# mbed-WiFi-BLE-Cloud-v1_1_0.net
KiCad netlist of a schematic drawn in EAGLE
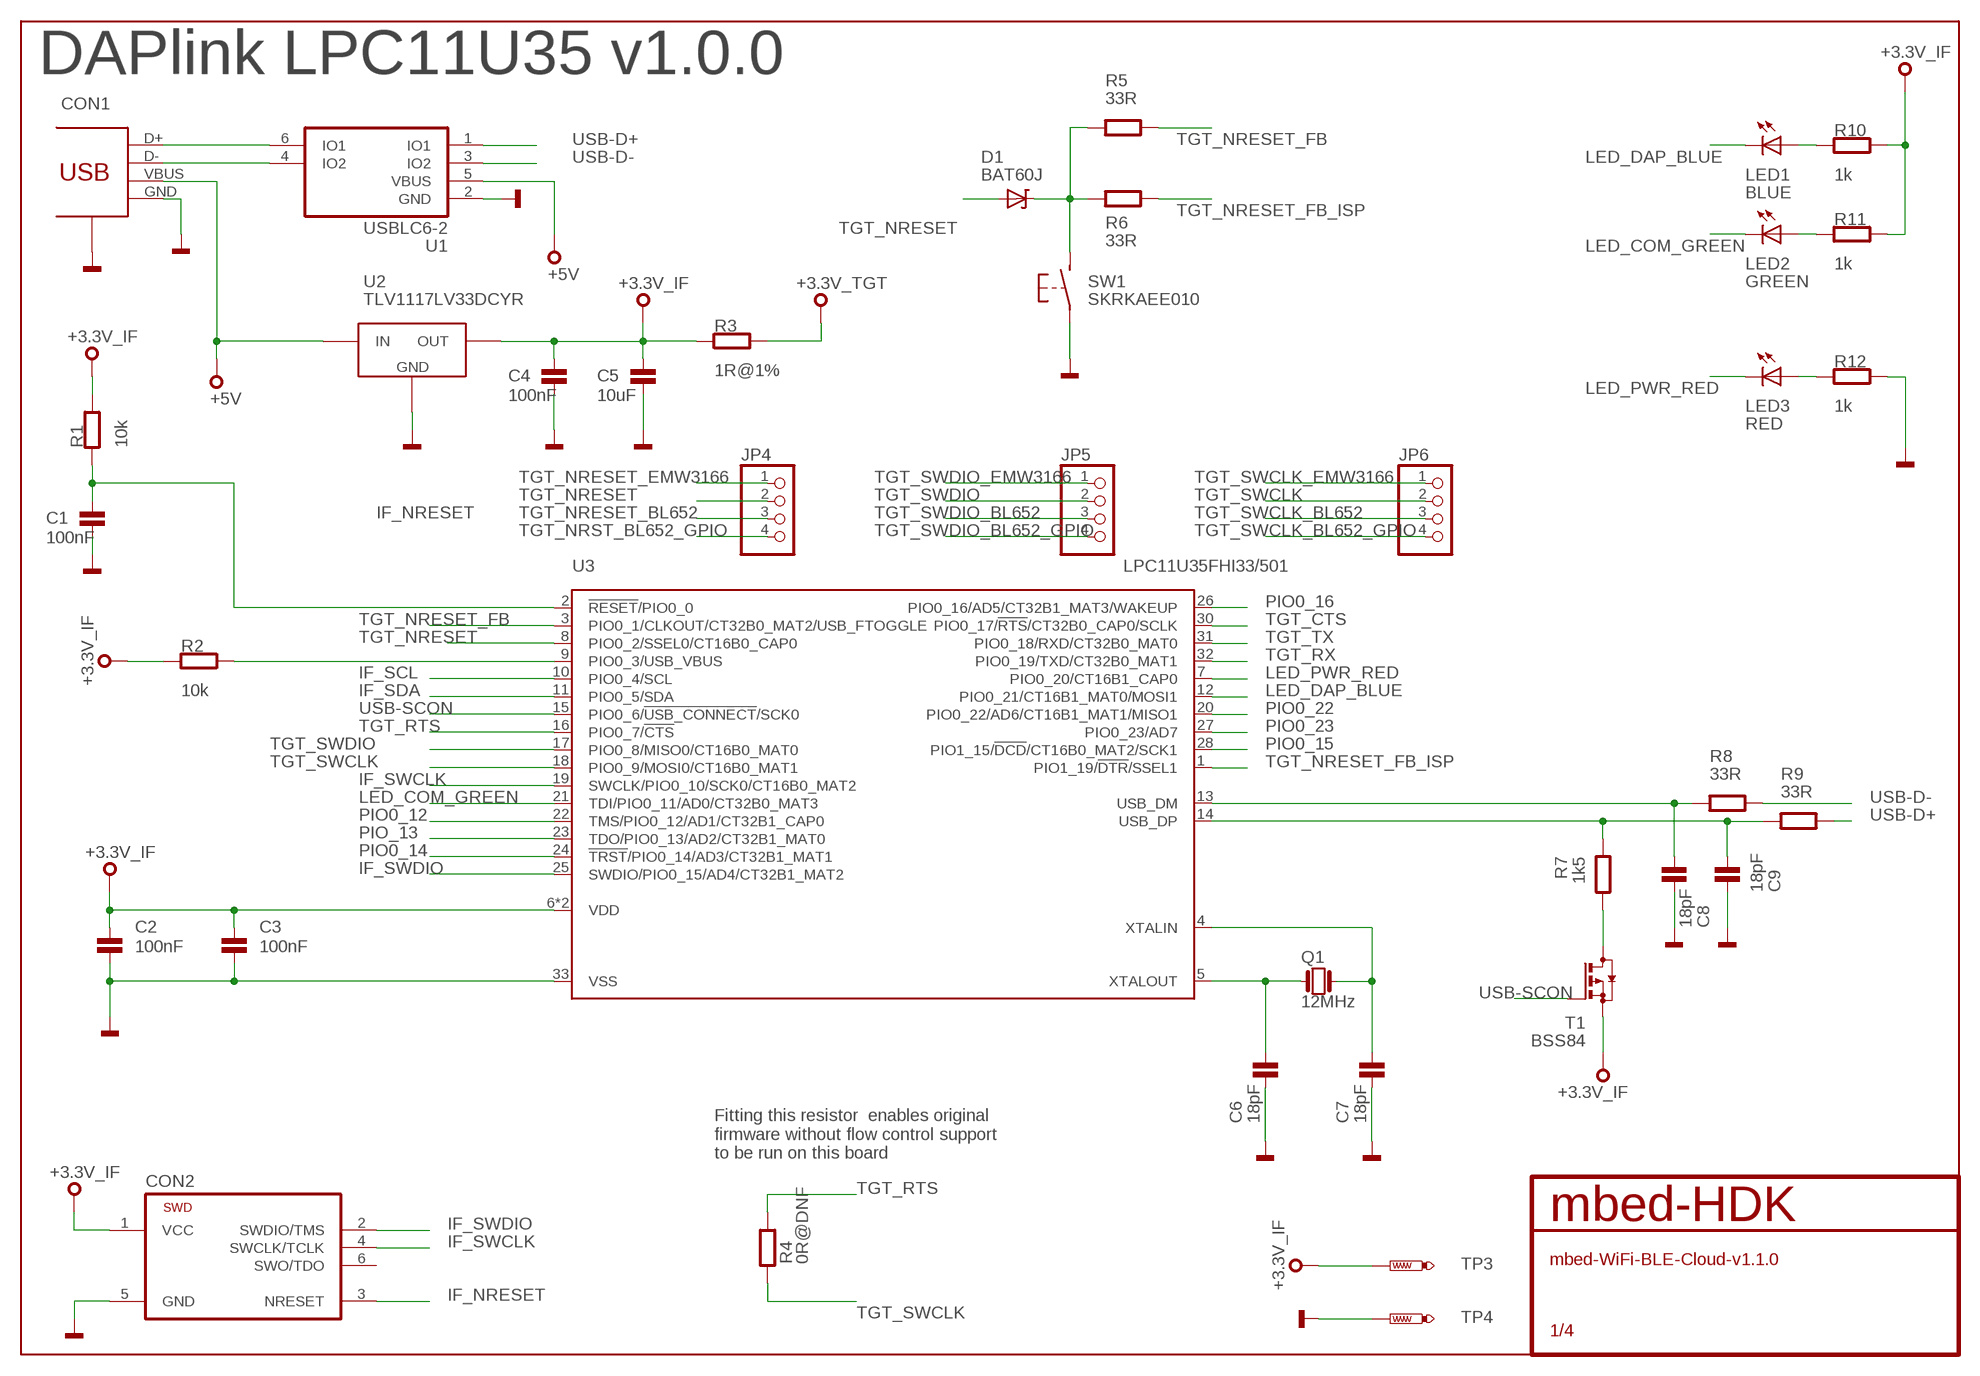
[diagram p0: schematic, sheet 1]
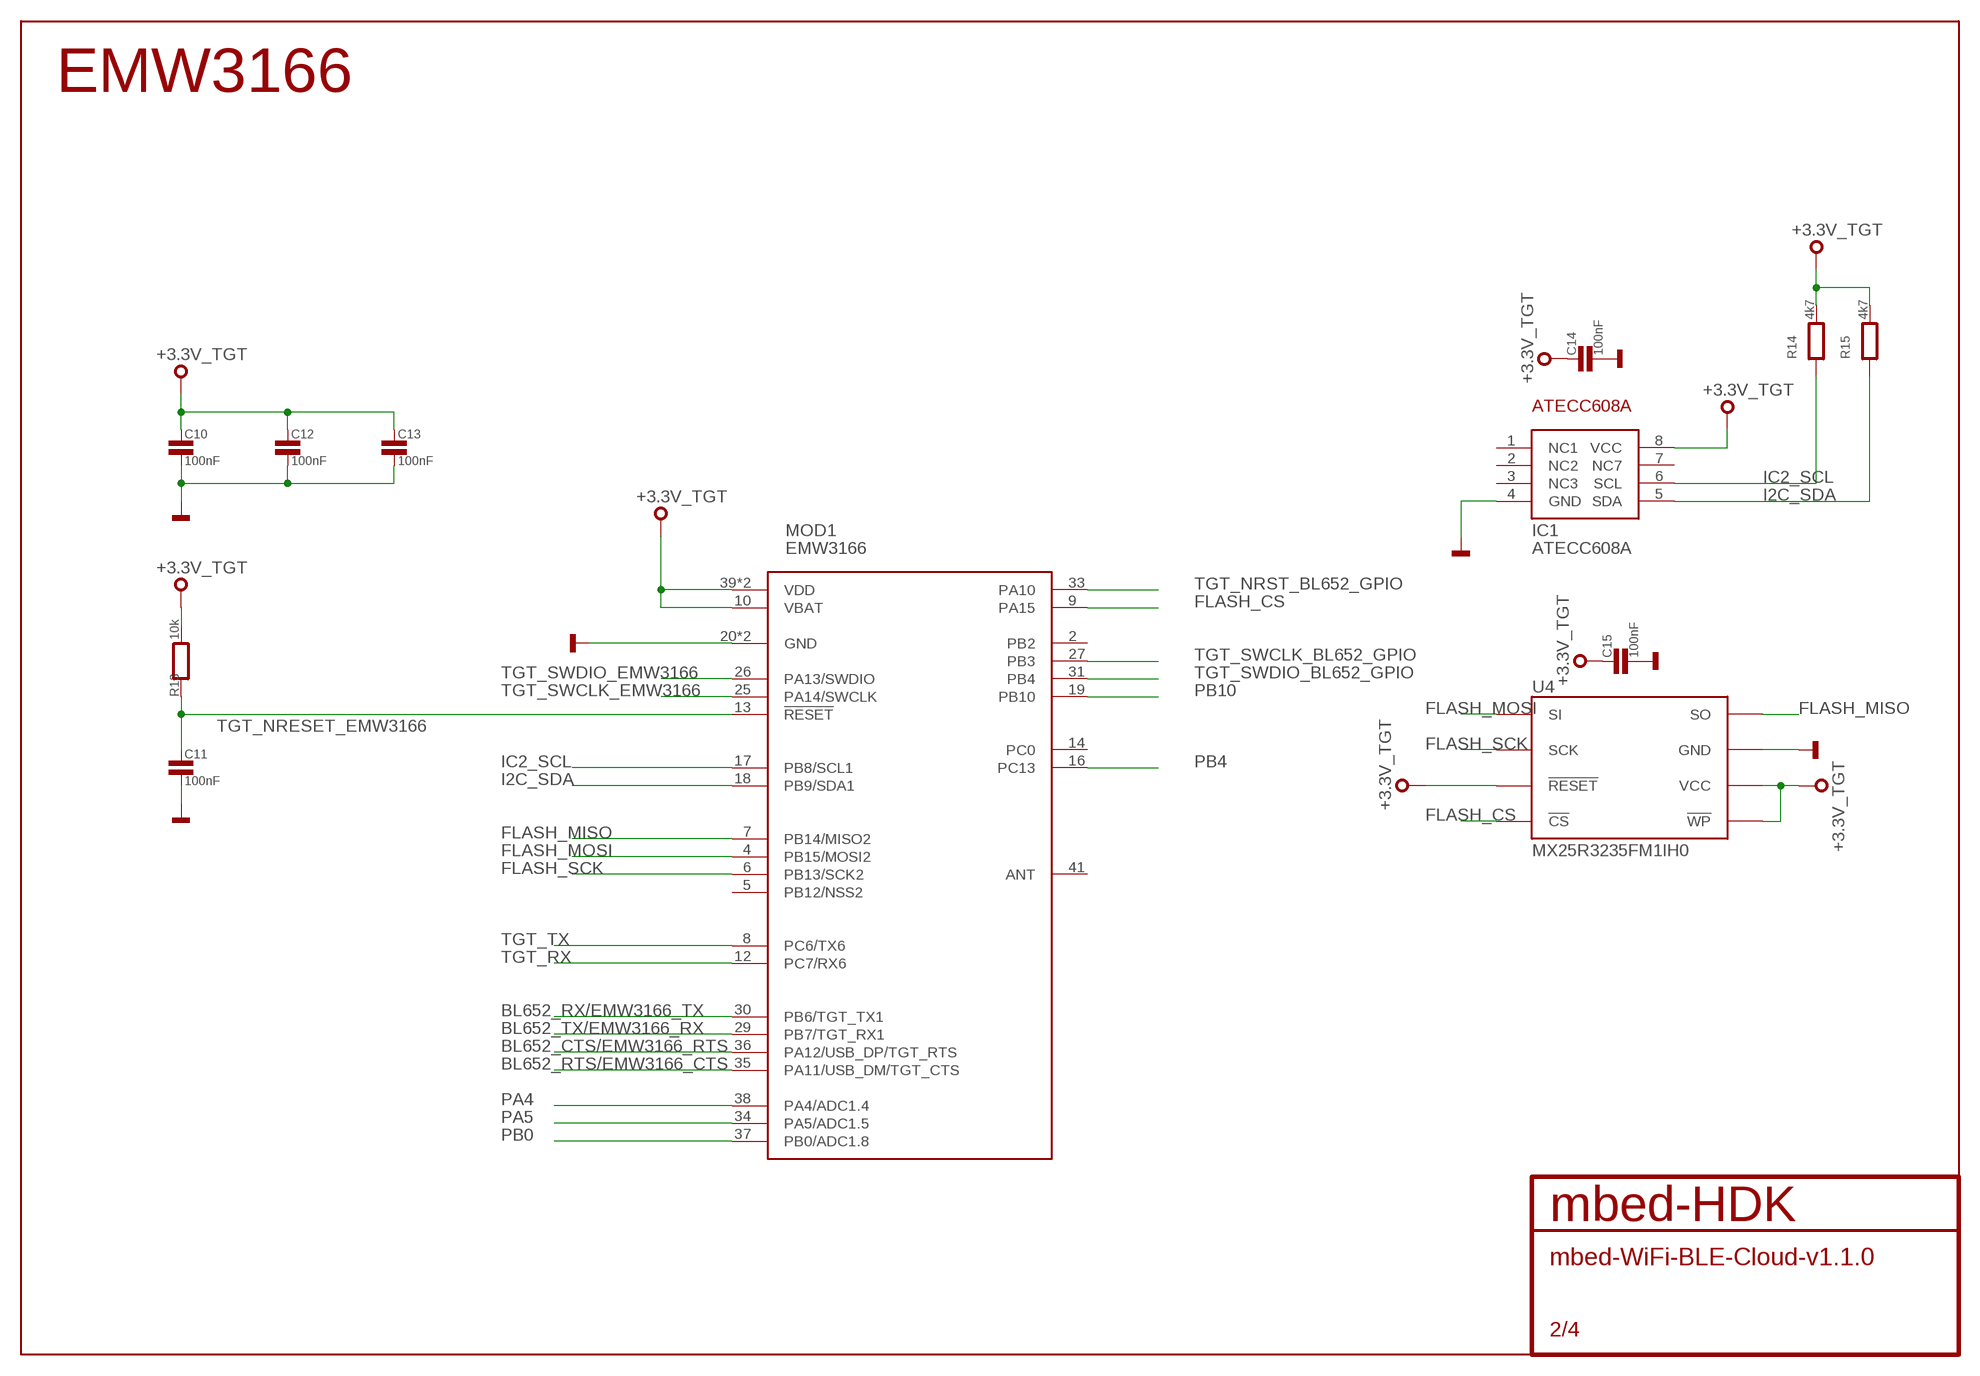
[diagram p1: schematic, sheet 2]
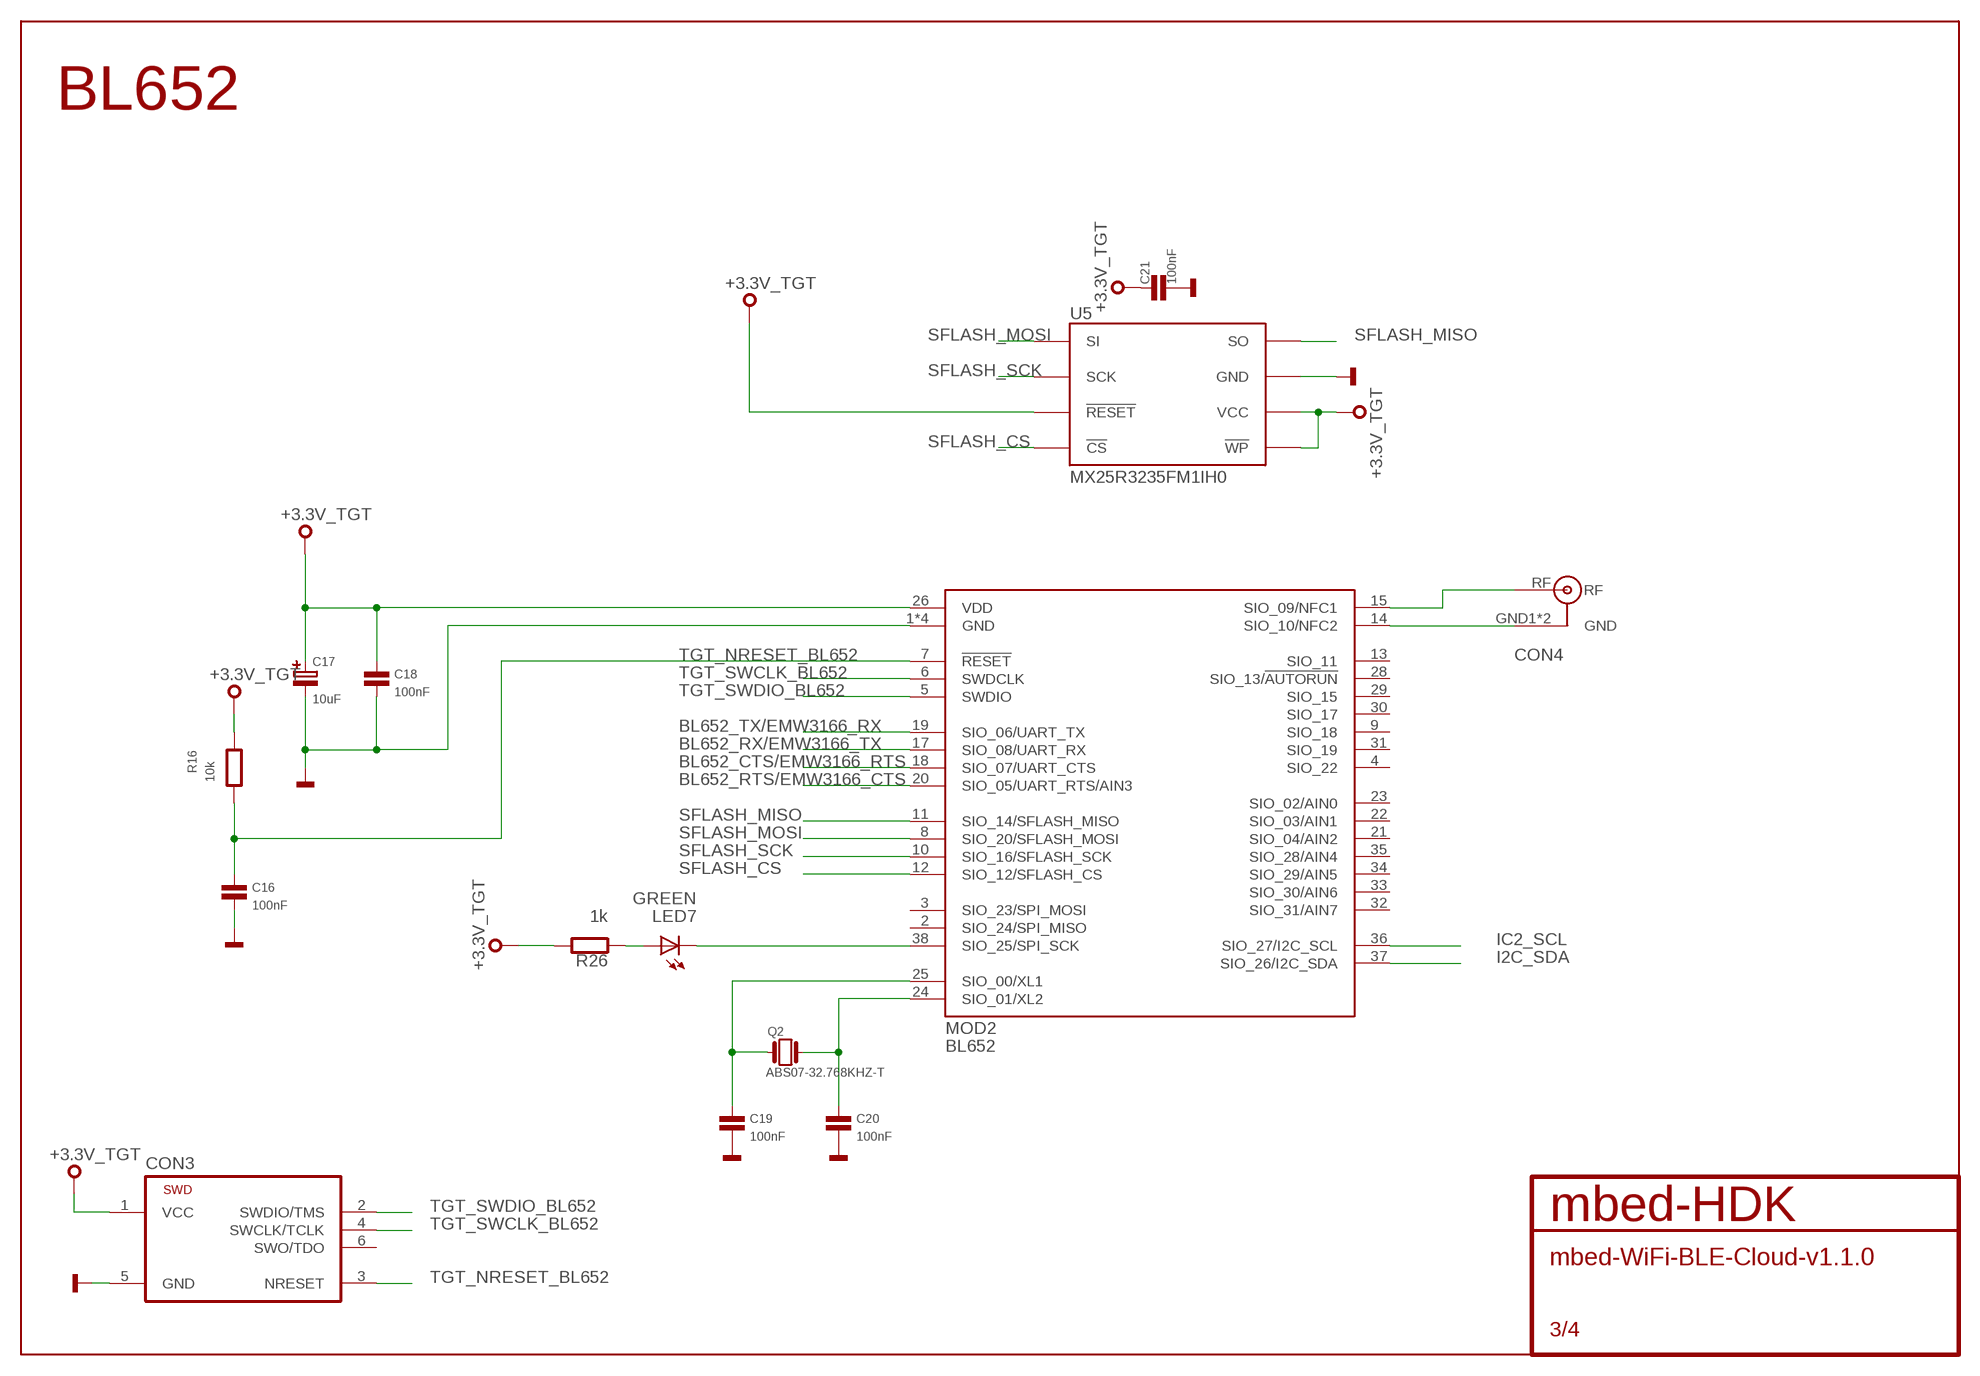
[diagram p2: schematic, sheet 3]
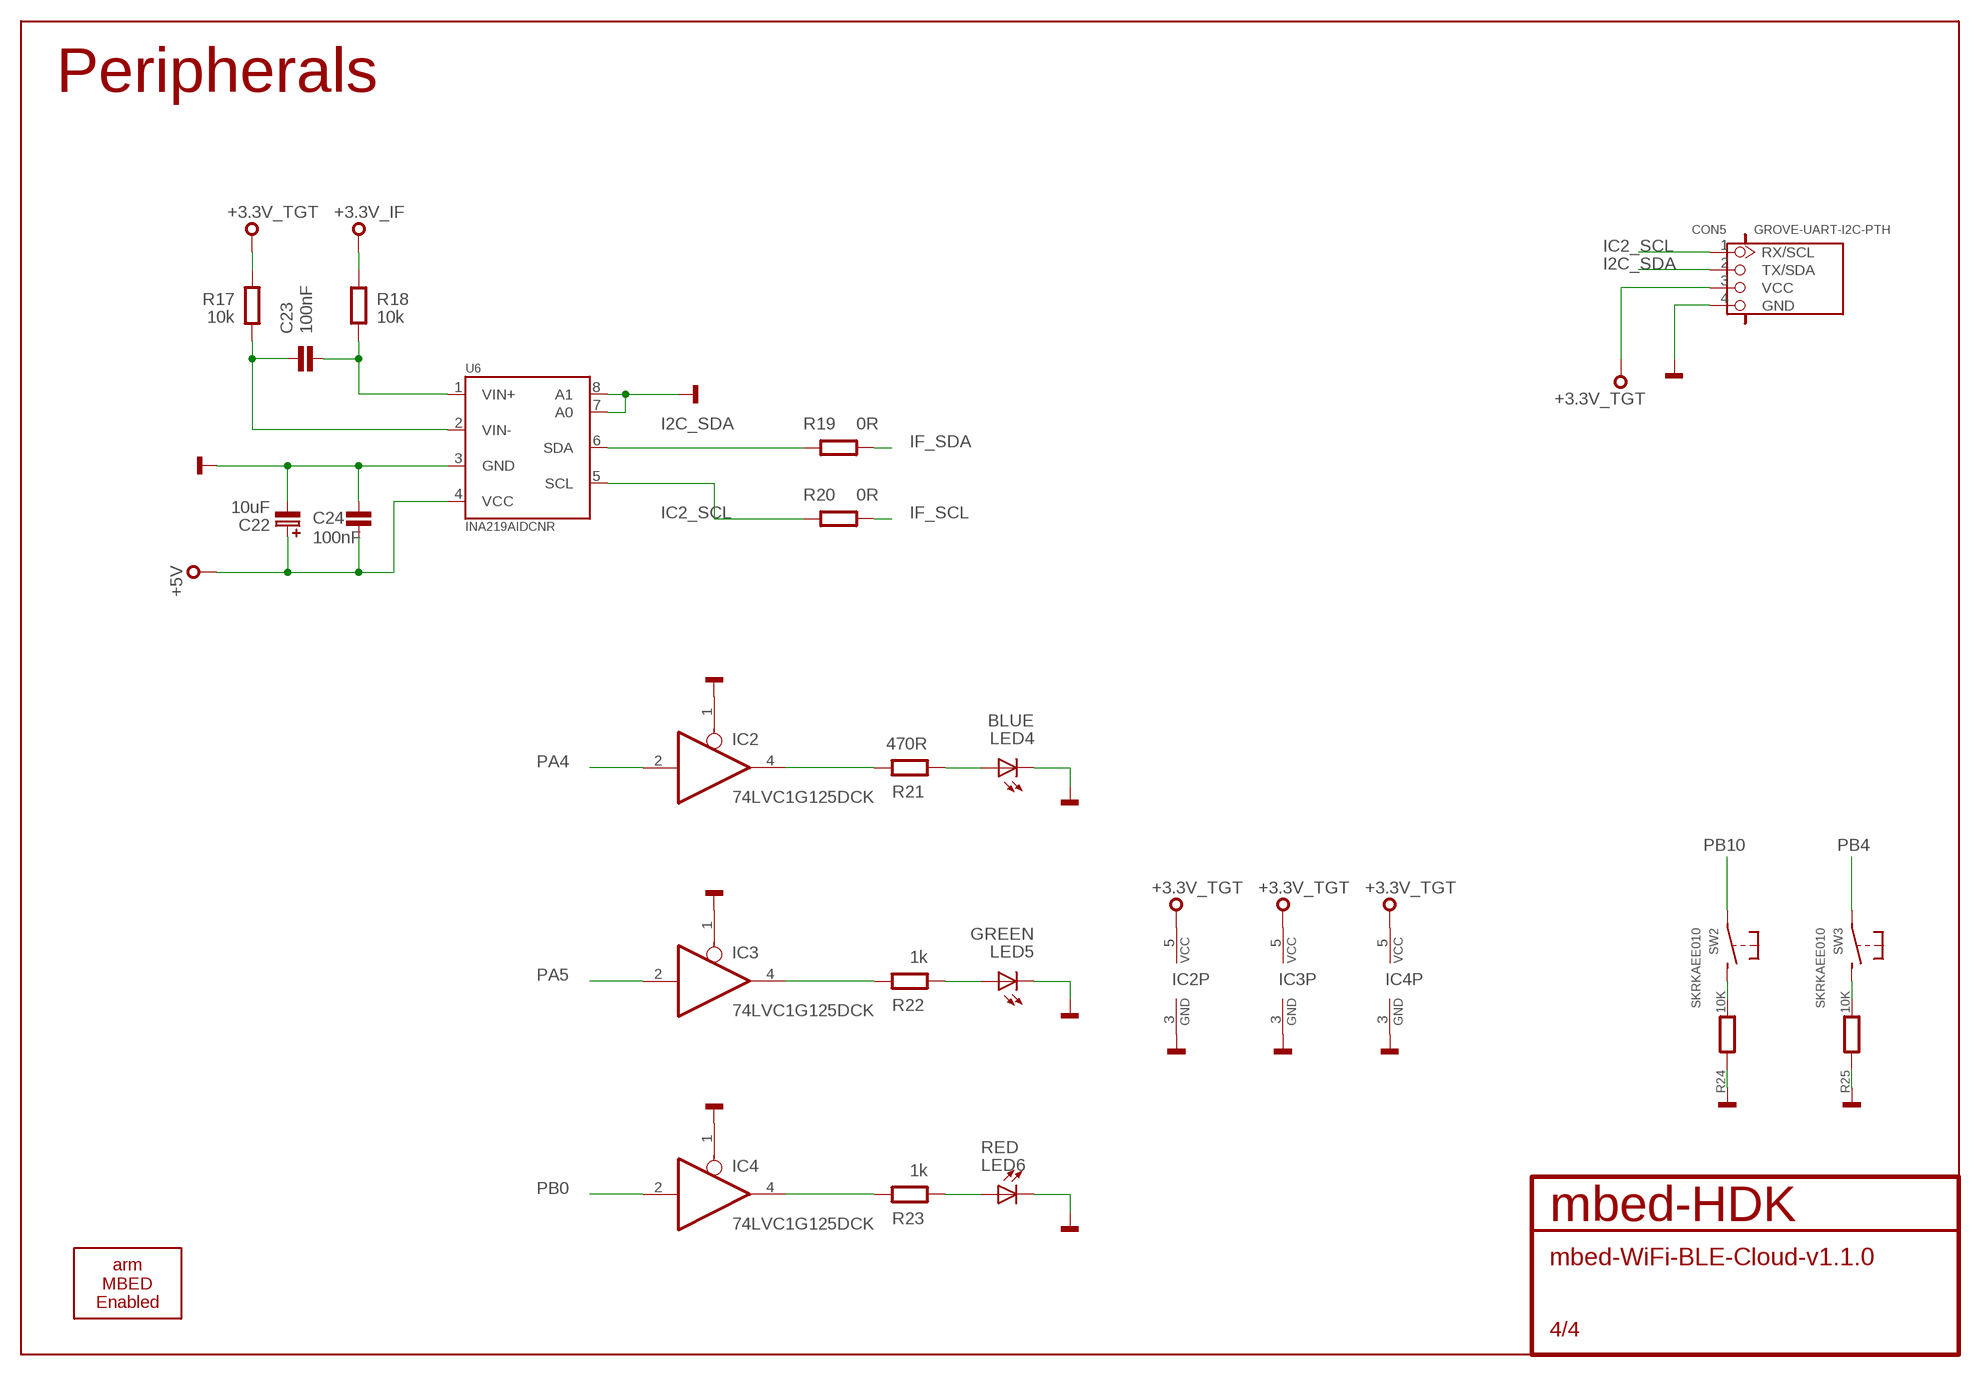
[diagram p3: schematic, sheet 4]

(export (version "E")
  (design (tool "Eeschema 10.0.6"))
  (components
    (comp (ref "C1")
      (value "100nF")
      (footprint "eagle-import:0603")
      (libsource (lib "eagle-import") (part "mbed-HDK-RLC_C0603"))
    )
    (comp (ref "C2")
      (value "100nF")
      (footprint "eagle-import:0603")
      (libsource (lib "eagle-import") (part "mbed-HDK-RLC_C0603"))
    )
    (comp (ref "C3")
      (value "100nF")
      (footprint "eagle-import:0603")
      (libsource (lib "eagle-import") (part "mbed-HDK-RLC_C0603"))
    )
    (comp (ref "C4")
      (value "100nF")
      (footprint "eagle-import:0603")
      (libsource (lib "eagle-import") (part "mbed-HDK-RLC_C0603"))
    )
    (comp (ref "C5")
      (value "10uF")
      (footprint "eagle-import:0603")
      (libsource (lib "eagle-import") (part "mbed-HDK-RLC_C0603"))
    )
    (comp (ref "C6")
      (value "18pF")
      (footprint "eagle-import:0603")
      (libsource (lib "eagle-import") (part "mbed-HDK-RLC_C0603"))
    )
    (comp (ref "C7")
      (value "18pF")
      (footprint "eagle-import:0603")
      (libsource (lib "eagle-import") (part "mbed-HDK-RLC_C0603"))
    )
    (comp (ref "C8")
      (value "18pF")
      (footprint "eagle-import:0603")
      (libsource (lib "eagle-import") (part "mbed-HDK-RLC_C0603"))
    )
    (comp (ref "C9")
      (value "18pF")
      (footprint "eagle-import:0603")
      (libsource (lib "eagle-import") (part "mbed-HDK-RLC_C0603"))
    )
    (comp (ref "CON1")
      (value "47346-0001")
      (footprint "eagle-import:USB-MICRO-B-H")
      (fields (field (name "MF") "MOLEX"))
      (libsource (lib "eagle-import") (part "47346-0001"))
    )
    (comp (ref "CON2")
      (value "TC2030-CTX-NL")
      (footprint "eagle-import:TC2030-CTX-NL")
      (libsource (lib "eagle-import") (part "TC2030-CTX-NL"))
    )
    (comp (ref "D1")
      (value "BAT60J")
      (footprint "eagle-import:SOD323")
      (fields (field (name "MF") "STMicroelectronics"))
      (libsource (lib "eagle-import") (part "BAT60J"))
    )
    (comp (ref "JP4")
      (value "PINHD-1X4")
      (footprint "eagle-import:1X04")
      (libsource (lib "eagle-import") (part "PINHD-1X4"))
    )
    (comp (ref "JP5")
      (value "PINHD-1X4")
      (footprint "eagle-import:1X04")
      (libsource (lib "eagle-import") (part "PINHD-1X4"))
    )
    (comp (ref "JP6")
      (value "PINHD-1X4")
      (footprint "eagle-import:1X04")
      (libsource (lib "eagle-import") (part "PINHD-1X4"))
    )
    (comp (ref "LED1")
      (value "BLUE")
      (footprint "eagle-import:CHIPLED_0603")
      (libsource (lib "eagle-import") (part "mbed-HDK-Optical_LED0603"))
    )
    (comp (ref "LED2")
      (value "GREEN")
      (footprint "eagle-import:CHIPLED_0603")
      (libsource (lib "eagle-import") (part "mbed-HDK-Optical_LED0603"))
    )
    (comp (ref "LED3")
      (value "RED")
      (footprint "eagle-import:CHIPLED_0603")
      (libsource (lib "eagle-import") (part "mbed-HDK-Optical_LED0603"))
    )
    (comp (ref "Q1")
      (value "12MHz")
      (footprint "eagle-import:3.2X2.5")
      (libsource (lib "eagle-import") (part "Q_3.2X2.5"))
    )
    (comp (ref "R1")
      (value "10k")
      (footprint "eagle-import:0603")
      (libsource (lib "eagle-import") (part "R0603"))
    )
    (comp (ref "R2")
      (value "10k")
      (footprint "eagle-import:0603")
      (libsource (lib "eagle-import") (part "R0603"))
    )
    (comp (ref "R3")
      (value "1R@1%")
      (footprint "eagle-import:0603")
      (libsource (lib "eagle-import") (part "R0603"))
    )
    (comp (ref "R4")
      (value "0R@DNF")
      (footprint "eagle-import:0603")
      (libsource (lib "eagle-import") (part "R0603"))
    )
    (comp (ref "R5")
      (value "33R")
      (footprint "eagle-import:0603")
      (libsource (lib "eagle-import") (part "R0603"))
    )
    (comp (ref "R6")
      (value "33R")
      (footprint "eagle-import:0603")
      (libsource (lib "eagle-import") (part "R0603"))
    )
    (comp (ref "R7")
      (value "1k5")
      (footprint "eagle-import:0603")
      (libsource (lib "eagle-import") (part "R0603"))
    )
    (comp (ref "R8")
      (value "33R")
      (footprint "eagle-import:0603")
      (libsource (lib "eagle-import") (part "R0603"))
    )
    (comp (ref "R9")
      (value "33R")
      (footprint "eagle-import:0603")
      (libsource (lib "eagle-import") (part "R0603"))
    )
    (comp (ref "R10")
      (value "1k")
      (footprint "eagle-import:0603")
      (libsource (lib "eagle-import") (part "R0603"))
    )
    (comp (ref "R11")
      (value "1k")
      (footprint "eagle-import:0603")
      (libsource (lib "eagle-import") (part "R0603"))
    )
    (comp (ref "R12")
      (value "1k")
      (footprint "eagle-import:0603")
      (libsource (lib "eagle-import") (part "R0603"))
    )
    (comp (ref "SW1")
      (value "SKRKAEE010")
      (footprint "eagle-import:SKRKAEE010")
      (fields (field (name "MF") "ALPS"))
      (libsource (lib "eagle-import") (part "SKRKAEE010"))
    )
    (comp (ref "T1")
      (value "BSS84")
      (footprint "eagle-import:SOT23-3")
      (fields (field (name "MF") "Fairchild Semiconductor"))
      (libsource (lib "eagle-import") (part "BSS84"))
    )
    (comp (ref "TP3")
      (value "PTR1PAD1-13")
      (footprint "eagle-import:P1-13")
      (libsource (lib "eagle-import") (part "PTR1PAD1-13"))
    )
    (comp (ref "TP4")
      (value "PTR1PAD1-13")
      (footprint "eagle-import:P1-13")
      (libsource (lib "eagle-import") (part "PTR1PAD1-13"))
    )
    (comp (ref "U1")
      (value "USBLC6-2SC6")
      (footprint "eagle-import:SOT23-6L")
      (fields (field (name "MF") "STMicro"))
      (libsource (lib "eagle-import") (part "USBLC6-2SC6"))
    )
    (comp (ref "U2")
      (value "TLV1117LV33DCYR")
      (footprint "eagle-import:SOT223")
      (fields (field (name "MF") "Texas Instruments"))
      (libsource (lib "eagle-import") (part "TLV1117LV33DCYR"))
    )
    (comp (ref "U3")
      (value "LPC11U35FHI33/501")
      (footprint "eagle-import:SOT617-3")
      (fields (field (name "MF") "NXP"))
      (libsource (lib "eagle-import") (part "LPC11U35FHI33/501"))
    )
    (comp (ref "C22")
      (value "10uF")
      (footprint "eagle-import:SMC_B")
      (fields (field (name "MF") "Kemet"))
      (libsource (lib "eagle-import") (part "C-POLB"))
    )
    (comp (ref "C23")
      (value "100nF")
      (footprint "eagle-import:0603")
      (libsource (lib "eagle-import") (part "C0603"))
    )
    (comp (ref "C24")
      (value "100nF")
      (footprint "eagle-import:0603")
      (libsource (lib "eagle-import") (part "C0603"))
    )
    (comp (ref "CON5")
      (value "GROVE-UART-I2C-PTH")
      (footprint "eagle-import:HW4-2.0")
      (libsource (lib "eagle-import") (part "GROVE-UART-I2C-PTH"))
    )
    (comp (ref "IC2")
      (value "74LVC1G125DCK")
      (footprint "eagle-import:SC70-5")
      (libsource (lib "eagle-import") (part "741G125DCKLVC"))
    )
    (comp (ref "IC3")
      (value "74LVC1G125DCK")
      (footprint "eagle-import:SC70-5")
      (libsource (lib "eagle-import") (part "741G125DCKLVC"))
    )
    (comp (ref "IC4")
      (value "74LVC1G125DCK")
      (footprint "eagle-import:SC70-5")
      (libsource (lib "eagle-import") (part "741G125DCKLVC"))
    )
    (comp (ref "LED4")
      (value "BLUE")
      (footprint "eagle-import:CHIPLED_0603")
      (libsource (lib "eagle-import") (part "LED0603"))
    )
    (comp (ref "LED5")
      (value "GREEN")
      (footprint "eagle-import:CHIPLED_0603")
      (libsource (lib "eagle-import") (part "LED0603"))
    )
    (comp (ref "LED6")
      (value "RED")
      (footprint "eagle-import:CHIPLED_0603")
      (libsource (lib "eagle-import") (part "LED0603"))
    )
    (comp (ref "R17")
      (value "10k")
      (footprint "eagle-import:0603")
      (libsource (lib "eagle-import") (part "R0603"))
    )
    (comp (ref "R18")
      (value "10k")
      (footprint "eagle-import:0603")
      (libsource (lib "eagle-import") (part "R0603"))
    )
    (comp (ref "R19")
      (value "0R")
      (footprint "eagle-import:0603")
      (libsource (lib "eagle-import") (part "R0603"))
    )
    (comp (ref "R20")
      (value "0R")
      (footprint "eagle-import:0603")
      (libsource (lib "eagle-import") (part "R0603"))
    )
    (comp (ref "R21")
      (value "470R")
      (footprint "eagle-import:0603")
      (libsource (lib "eagle-import") (part "R0603"))
    )
    (comp (ref "R22")
      (value "1k")
      (footprint "eagle-import:0603")
      (libsource (lib "eagle-import") (part "R0603"))
    )
    (comp (ref "R23")
      (value "1k")
      (footprint "eagle-import:0603")
      (libsource (lib "eagle-import") (part "R0603"))
    )
    (comp (ref "R24")
      (value "10K")
      (footprint "eagle-import:0603")
      (libsource (lib "eagle-import") (part "R0603"))
    )
    (comp (ref "R25")
      (value "10K")
      (footprint "eagle-import:0603")
      (libsource (lib "eagle-import") (part "R0603"))
    )
    (comp (ref "SS1")
      (value "ARM-MBED-ENABLED-12MM")
      (footprint "eagle-import:ARM-MBED-ENABLED-12MM")
      (libsource (lib "eagle-import") (part "ARM-MBED-ENABLED-12MM"))
    )
    (comp (ref "SW2")
      (value "SKRKAEE010")
      (footprint "eagle-import:SKRKAEE010")
      (fields (field (name "MF") "ALPS"))
      (libsource (lib "eagle-import") (part "SKRKAEE010"))
    )
    (comp (ref "SW3")
      (value "SKRKAEE010")
      (footprint "eagle-import:SKRKAEE010")
      (fields (field (name "MF") "ALPS"))
      (libsource (lib "eagle-import") (part "SKRKAEE010"))
    )
    (comp (ref "U6")
      (value "INA219AIDCNR")
      (footprint "eagle-import:SOT23-8")
      (fields (field (name "MF") "Texas Instruments"))
      (libsource (lib "eagle-import") (part "INA219AIDCNR"))
    )
    (comp (ref "C16")
      (value "100nF")
      (footprint "eagle-import:0603")
      (libsource (lib "eagle-import") (part "C0603"))
    )
    (comp (ref "C17")
      (value "10uF")
      (footprint "eagle-import:SMC_B")
      (fields (field (name "MF") "Kemet"))
      (libsource (lib "eagle-import") (part "C-POLB"))
    )
    (comp (ref "C18")
      (value "100nF")
      (footprint "eagle-import:0603")
      (libsource (lib "eagle-import") (part "C0603"))
    )
    (comp (ref "C19")
      (value "100nF")
      (footprint "eagle-import:0603")
      (libsource (lib "eagle-import") (part "C0603"))
    )
    (comp (ref "C20")
      (value "100nF")
      (footprint "eagle-import:0603")
      (libsource (lib "eagle-import") (part "C0603"))
    )
    (comp (ref "C21")
      (value "100nF")
      (footprint "eagle-import:0603")
      (libsource (lib "eagle-import") (part "mbed-HDK-RLC_C0603"))
    )
    (comp (ref "CON3")
      (value "TC2030-CTX-NL")
      (footprint "eagle-import:TC2030-CTX-NL")
      (libsource (lib "eagle-import") (part "TC2030-CTX-NL"))
    )
    (comp (ref "CON4")
      (value "U.FL")
      (footprint "eagle-import:U.FL-R-SMT-1")
      (fields (field (name "MF") "Hirose"))
      (libsource (lib "eagle-import") (part "U.FL"))
    )
    (comp (ref "LED7")
      (value "GREEN")
      (footprint "eagle-import:CHIPLED_0603")
      (libsource (lib "eagle-import") (part "mbed-HDK-Optical_LED0603"))
    )
    (comp (ref "MOD2")
      (value "BL652")
      (footprint "eagle-import:BL652")
      (libsource (lib "eagle-import") (part "BL652"))
    )
    (comp (ref "Q2")
      (value "ABS07-32.768KHZ-T")
      (footprint "eagle-import:FC135")
      (fields (field (name "MF") "Abracon"))
      (libsource (lib "eagle-import") (part "ABS07-32.768KHZ-T"))
    )
    (comp (ref "R16")
      (value "10k")
      (footprint "eagle-import:0603")
      (libsource (lib "eagle-import") (part "R0603"))
    )
    (comp (ref "R26")
      (value "1k")
      (footprint "eagle-import:0603")
      (libsource (lib "eagle-import") (part "R0603"))
    )
    (comp (ref "U5")
      (value "MX25R3235FM1IH0")
      (footprint "eagle-import:SO8")
      (fields (field (name "MF") "Macronix"))
      (libsource (lib "eagle-import") (part "MX25R3235FM1IH0"))
    )
    (comp (ref "C10")
      (value "100nF")
      (footprint "eagle-import:0603")
      (libsource (lib "eagle-import") (part "mbed-HDK-RLC_C0603"))
    )
    (comp (ref "C11")
      (value "100nF")
      (footprint "eagle-import:0603")
      (libsource (lib "eagle-import") (part "mbed-HDK-RLC_C0603"))
    )
    (comp (ref "C12")
      (value "100nF")
      (footprint "eagle-import:0603")
      (libsource (lib "eagle-import") (part "mbed-HDK-RLC_C0603"))
    )
    (comp (ref "C13")
      (value "100nF")
      (footprint "eagle-import:0603")
      (libsource (lib "eagle-import") (part "mbed-HDK-RLC_C0603"))
    )
    (comp (ref "C14")
      (value "100nF")
      (footprint "eagle-import:0603")
      (libsource (lib "eagle-import") (part "mbed-HDK-RLC_C0603"))
    )
    (comp (ref "C15")
      (value "100nF")
      (footprint "eagle-import:0603")
      (libsource (lib "eagle-import") (part "mbed-HDK-RLC_C0603"))
    )
    (comp (ref "IC1")
      (value "ATECC608A")
      (footprint "eagle-import:SO8")
      (libsource (lib "eagle-import") (part "ATECC608A"))
    )
    (comp (ref "MOD1")
      (value "EMW3166")
      (footprint "eagle-import:EMW3166")
      (libsource (lib "eagle-import") (part "EMW3166"))
    )
    (comp (ref "R13")
      (value "10k")
      (footprint "eagle-import:0603")
      (libsource (lib "eagle-import") (part "R0603"))
    )
    (comp (ref "R14")
      (value "4k7")
      (footprint "eagle-import:0603")
      (libsource (lib "eagle-import") (part "R0603"))
    )
    (comp (ref "R15")
      (value "4k7")
      (footprint "eagle-import:0603")
      (libsource (lib "eagle-import") (part "R0603"))
    )
    (comp (ref "U4")
      (value "MX25R3235FM1IH0")
      (footprint "eagle-import:SO8")
      (fields (field (name "MF") "Macronix"))
      (libsource (lib "eagle-import") (part "MX25R3235FM1IH0"))
    )
  )
  (nets
    (net (code "1") (name "+3.3V_IF") (class "Default")
      (node (ref "C2") (pin "1") (pinfunction "P$1_1") (pintype "passive"))
      (node (ref "C3") (pin "1") (pinfunction "P$1_1") (pintype "passive"))
      (node (ref "C4") (pin "1") (pinfunction "P$1_1") (pintype "passive"))
      (node (ref "C5") (pin "1") (pinfunction "P$1_1") (pintype "passive"))
      (node (ref "CON2") (pin "1") (pinfunction "VCC_1") (pintype "passive"))
      (node (ref "R1") (pin "2") (pinfunction "P$2_2") (pintype "passive"))
      (node (ref "R10") (pin "2") (pinfunction "P$2_2") (pintype "passive"))
      (node (ref "R11") (pin "2") (pinfunction "P$2_2") (pintype "passive"))
      (node (ref "R18") (pin "2") (pinfunction "P$2_2") (pintype "passive"))
      (node (ref "R2") (pin "1") (pinfunction "P$1_1") (pintype "passive"))
      (node (ref "R3") (pin "1") (pinfunction "P$1_1") (pintype "passive"))
      (node (ref "T1") (pin "2") (pinfunction "S_2") (pintype "passive"))
      (node (ref "TP3") (pin "TP") (pinfunction "TP_TP") (pintype "input"))
      (node (ref "U2") (pin "2") (pinfunction "OUT_2") (pintype "bidirectional"))
      (node (ref "U2") (pin "4") (pinfunction "OUT_4") (pintype "bidirectional"))
      (node (ref "U3") (pin "29") (pinfunction "VDD_29") (pintype "passive"))
      (node (ref "U3") (pin "6") (pinfunction "VDD_6") (pintype "passive"))
    )
    (net (code "2") (name "+3.3V_TGT") (class "Default")
      (node (ref "C10") (pin "1") (pinfunction "P$1_1") (pintype "passive"))
      (node (ref "C12") (pin "1") (pinfunction "P$1_1") (pintype "passive"))
      (node (ref "C13") (pin "1") (pinfunction "P$1_1") (pintype "passive"))
      (node (ref "C14") (pin "1") (pinfunction "P$1_1") (pintype "passive"))
      (node (ref "C15") (pin "1") (pinfunction "P$1_1") (pintype "passive"))
      (node (ref "C17") (pin "+") (pinfunction "+_+") (pintype "passive"))
      (node (ref "C18") (pin "1") (pinfunction "P$1_1") (pintype "passive"))
      (node (ref "C21") (pin "1") (pinfunction "P$1_1") (pintype "passive"))
      (node (ref "CON3") (pin "1") (pinfunction "VCC_1") (pintype "passive"))
      (node (ref "CON5") (pin "3") (pinfunction "VCC_3") (pintype "bidirectional"))
      (node (ref "IC1") (pin "8") (pinfunction "VCC_8") (pintype "bidirectional"))
      (node (ref "IC2") (pin "5") (pinfunction "VCC_5") (pintype "power_in"))
      (node (ref "IC3") (pin "5") (pinfunction "VCC_5") (pintype "power_in"))
      (node (ref "IC4") (pin "5") (pinfunction "VCC_5") (pintype "power_in"))
      (node (ref "MOD1") (pin "10") (pinfunction "VBAT_10") (pintype "bidirectional"))
      (node (ref "MOD1") (pin "39") (pinfunction "VDD_39") (pintype "bidirectional"))
      (node (ref "MOD1") (pin "40") (pinfunction "VDD_40") (pintype "bidirectional"))
      (node (ref "MOD2") (pin "26") (pinfunction "VDD_26") (pintype "bidirectional"))
      (node (ref "R13") (pin "2") (pinfunction "P$2_2") (pintype "passive"))
      (node (ref "R14") (pin "2") (pinfunction "P$2_2") (pintype "passive"))
      (node (ref "R15") (pin "2") (pinfunction "P$2_2") (pintype "passive"))
      (node (ref "R16") (pin "2") (pinfunction "P$2_2") (pintype "passive"))
      (node (ref "R17") (pin "2") (pinfunction "P$2_2") (pintype "passive"))
      (node (ref "R26") (pin "2") (pinfunction "P$2_2") (pintype "passive"))
      (node (ref "R3") (pin "2") (pinfunction "P$2_2") (pintype "passive"))
      (node (ref "U4") (pin "3") (pinfunction "~{WP}_3") (pintype "bidirectional"))
      (node (ref "U4") (pin "7") (pinfunction "~{RESET}_7") (pintype "bidirectional"))
      (node (ref "U4") (pin "8") (pinfunction "VCC_8") (pintype "bidirectional"))
      (node (ref "U5") (pin "3") (pinfunction "~{WP}_3") (pintype "bidirectional"))
      (node (ref "U5") (pin "7") (pinfunction "~{RESET}_7") (pintype "bidirectional"))
      (node (ref "U5") (pin "8") (pinfunction "VCC_8") (pintype "bidirectional"))
    )
    (net (code "3") (name "+5V") (class "Default")
      (node (ref "C22") (pin "+") (pinfunction "+_+") (pintype "passive"))
      (node (ref "C24") (pin "2") (pinfunction "P$2_2") (pintype "passive"))
      (node (ref "CON1") (pin "VBUS") (pinfunction "VBUS_VBUS") (pintype "bidirectional"))
      (node (ref "U1") (pin "5") (pinfunction "VBUS_5") (pintype "bidirectional"))
      (node (ref "U2") (pin "3") (pinfunction "IN_3") (pintype "bidirectional"))
      (node (ref "U6") (pin "4") (pinfunction "VCC_4") (pintype "power_in"))
    )
    (net (code "4") (name "BL652_CTS{slash}EMW3166_RTS") (class "Default")
      (node (ref "MOD1") (pin "36") (pinfunction "PA12/USB_DP/TGT_RTS_36") (pintype "bidirectional"))
      (node (ref "MOD2") (pin "18") (pinfunction "SIO_07/UART_CTS_18") (pintype "bidirectional"))
    )
    (net (code "5") (name "BL652_RTS{slash}EMW3166_CTS") (class "Default")
      (node (ref "MOD1") (pin "35") (pinfunction "PA11/USB_DM/TGT_CTS_35") (pintype "bidirectional"))
      (node (ref "MOD2") (pin "20") (pinfunction "SIO_05/UART_RTS/AIN3_20") (pintype "bidirectional"))
    )
    (net (code "6") (name "BL652_RX{slash}EMW3166_TX") (class "Default")
      (node (ref "MOD1") (pin "30") (pinfunction "PB6/TGT_TX1_30") (pintype "bidirectional"))
      (node (ref "MOD2") (pin "17") (pinfunction "SIO_08/UART_RX_17") (pintype "bidirectional"))
    )
    (net (code "7") (name "BL652_TX{slash}EMW3166_RX") (class "Default")
      (node (ref "MOD1") (pin "29") (pinfunction "PB7/TGT_RX1_29") (pintype "bidirectional"))
      (node (ref "MOD2") (pin "19") (pinfunction "SIO_06/UART_TX_19") (pintype "bidirectional"))
    )
    (net (code "8") (name "FLASH_CS") (class "Default")
      (node (ref "MOD1") (pin "9") (pinfunction "PA15_9") (pintype "bidirectional"))
      (node (ref "U4") (pin "1") (pinfunction "~{CS}_1") (pintype "bidirectional"))
    )
    (net (code "9") (name "FLASH_MISO") (class "Default")
      (node (ref "MOD1") (pin "7") (pinfunction "PB14/MISO2_7") (pintype "bidirectional"))
      (node (ref "U4") (pin "2") (pinfunction "SO_2") (pintype "bidirectional"))
    )
    (net (code "10") (name "FLASH_MOSI") (class "Default")
      (node (ref "MOD1") (pin "4") (pinfunction "PB15/MOSI2_4") (pintype "bidirectional"))
      (node (ref "U4") (pin "5") (pinfunction "SI_5") (pintype "bidirectional"))
    )
    (net (code "11") (name "FLASH_SCK") (class "Default")
      (node (ref "MOD1") (pin "6") (pinfunction "PB13/SCK2_6") (pintype "bidirectional"))
      (node (ref "U4") (pin "6") (pinfunction "SCK_6") (pintype "bidirectional"))
    )
    (net (code "12") (name "GND") (class "Default")
      (node (ref "C1") (pin "2") (pinfunction "P$2_2") (pintype "passive"))
      (node (ref "C10") (pin "2") (pinfunction "P$2_2") (pintype "passive"))
      (node (ref "C11") (pin "2") (pinfunction "P$2_2") (pintype "passive"))
      (node (ref "C12") (pin "2") (pinfunction "P$2_2") (pintype "passive"))
      (node (ref "C13") (pin "2") (pinfunction "P$2_2") (pintype "passive"))
      (node (ref "C14") (pin "2") (pinfunction "P$2_2") (pintype "passive"))
      (node (ref "C15") (pin "2") (pinfunction "P$2_2") (pintype "passive"))
      (node (ref "C16") (pin "2") (pinfunction "P$2_2") (pintype "passive"))
      (node (ref "C17") (pin "-") (pinfunction "-_-") (pintype "passive"))
      (node (ref "C18") (pin "2") (pinfunction "P$2_2") (pintype "passive"))
      (node (ref "C19") (pin "2") (pinfunction "P$2_2") (pintype "passive"))
      (node (ref "C2") (pin "2") (pinfunction "P$2_2") (pintype "passive"))
      (node (ref "C20") (pin "2") (pinfunction "P$2_2") (pintype "passive"))
      (node (ref "C21") (pin "2") (pinfunction "P$2_2") (pintype "passive"))
      (node (ref "C22") (pin "-") (pinfunction "-_-") (pintype "passive"))
      (node (ref "C24") (pin "1") (pinfunction "P$1_1") (pintype "passive"))
      (node (ref "C3") (pin "2") (pinfunction "P$2_2") (pintype "passive"))
      (node (ref "C4") (pin "2") (pinfunction "P$2_2") (pintype "passive"))
      (node (ref "C5") (pin "2") (pinfunction "P$2_2") (pintype "passive"))
      (node (ref "C6") (pin "2") (pinfunction "P$2_2") (pintype "passive"))
      (node (ref "C7") (pin "2") (pinfunction "P$2_2") (pintype "passive"))
      (node (ref "C8") (pin "2") (pinfunction "P$2_2") (pintype "passive"))
      (node (ref "C9") (pin "2") (pinfunction "P$2_2") (pintype "passive"))
      (node (ref "CON1") (pin "GND") (pinfunction "GND_GND") (pintype "bidirectional"))
      (node (ref "CON1") (pin "GND1") (pinfunction "SHEILD_GND1") (pintype "bidirectional"))
      (node (ref "CON1") (pin "GND2") (pinfunction "SHEILD_GND2") (pintype "bidirectional"))
      (node (ref "CON1") (pin "GND3") (pinfunction "SHEILD_GND3") (pintype "bidirectional"))
      (node (ref "CON1") (pin "GND4") (pinfunction "SHEILD_GND4") (pintype "bidirectional"))
      (node (ref "CON2") (pin "5") (pinfunction "GND_5") (pintype "passive"))
      (node (ref "CON3") (pin "5") (pinfunction "GND_5") (pintype "passive"))
      (node (ref "CON5") (pin "4") (pinfunction "GND_4") (pintype "bidirectional"))
      (node (ref "IC1") (pin "4") (pinfunction "GND_4") (pintype "bidirectional"))
      (node (ref "IC2") (pin "1") (pinfunction "OE_1") (pintype "input"))
      (node (ref "IC2") (pin "3") (pinfunction "GND_3") (pintype "power_in"))
      (node (ref "IC3") (pin "1") (pinfunction "OE_1") (pintype "input"))
      (node (ref "IC3") (pin "3") (pinfunction "GND_3") (pintype "power_in"))
      (node (ref "IC4") (pin "1") (pinfunction "OE_1") (pintype "input"))
      (node (ref "IC4") (pin "3") (pinfunction "GND_3") (pintype "power_in"))
      (node (ref "LED4") (pin "C") (pinfunction "C_C") (pintype "passive"))
      (node (ref "LED5") (pin "C") (pinfunction "C_C") (pintype "passive"))
      (node (ref "LED6") (pin "C") (pinfunction "C_C") (pintype "passive"))
      (node (ref "MOD1") (pin "20") (pinfunction "GND_20") (pintype "bidirectional"))
      (node (ref "MOD1") (pin "21") (pinfunction "GND_21") (pintype "bidirectional"))
      (node (ref "MOD2") (pin "1") (pinfunction "GND_1") (pintype "bidirectional"))
      (node (ref "MOD2") (pin "16") (pinfunction "GND_16") (pintype "bidirectional"))
      (node (ref "MOD2") (pin "27") (pinfunction "GND_27") (pintype "bidirectional"))
      (node (ref "MOD2") (pin "39") (pinfunction "GND_39") (pintype "bidirectional"))
      (node (ref "R12") (pin "2") (pinfunction "P$2_2") (pintype "passive"))
      (node (ref "R24") (pin "1") (pinfunction "P$1_1") (pintype "passive"))
      (node (ref "R25") (pin "1") (pinfunction "P$1_1") (pintype "passive"))
      (node (ref "SW1") (pin "P$1") (pinfunction "P_P$1") (pintype "passive"))
      (node (ref "TP4") (pin "TP") (pinfunction "TP_TP") (pintype "input"))
      (node (ref "U1") (pin "2") (pinfunction "GND_2") (pintype "bidirectional"))
      (node (ref "U2") (pin "1") (pinfunction "GND_1") (pintype "bidirectional"))
      (node (ref "U3") (pin "33") (pinfunction "VSS_33") (pintype "passive"))
      (node (ref "U4") (pin "4") (pinfunction "GND_4") (pintype "bidirectional"))
      (node (ref "U5") (pin "4") (pinfunction "GND_4") (pintype "bidirectional"))
      (node (ref "U6") (pin "3") (pinfunction "GND_3") (pintype "power_in"))
      (node (ref "U6") (pin "7") (pinfunction "A0_7") (pintype "input"))
      (node (ref "U6") (pin "8") (pinfunction "A1_8") (pintype "input"))
    )
    (net (code "13") (name "I2C_SDA") (class "Default")
      (node (ref "CON5") (pin "2") (pinfunction "TX/SDA_2") (pintype "bidirectional"))
      (node (ref "IC1") (pin "5") (pinfunction "SDA_5") (pintype "bidirectional"))
      (node (ref "MOD1") (pin "18") (pinfunction "PB9/SDA1_18") (pintype "bidirectional"))
      (node (ref "MOD2") (pin "37") (pinfunction "SIO_26/I2C_SDA_37") (pintype "bidirectional"))
      (node (ref "R15") (pin "1") (pinfunction "P$1_1") (pintype "passive"))
      (node (ref "R19") (pin "2") (pinfunction "P$2_2") (pintype "passive"))
      (node (ref "U6") (pin "6") (pinfunction "SDA_6") (pintype "bidirectional"))
    )
    (net (code "14") (name "IC2_SCL") (class "Default")
      (node (ref "CON5") (pin "1") (pinfunction "RX/SCL_1") (pintype "bidirectional"))
      (node (ref "IC1") (pin "6") (pinfunction "SCL_6") (pintype "bidirectional"))
      (node (ref "MOD1") (pin "17") (pinfunction "PB8/SCL1_17") (pintype "bidirectional"))
      (node (ref "MOD2") (pin "36") (pinfunction "SIO_27/I2C_SCL_36") (pintype "bidirectional"))
      (node (ref "R14") (pin "1") (pinfunction "P$1_1") (pintype "passive"))
      (node (ref "R20") (pin "2") (pinfunction "P$2_2") (pintype "passive"))
      (node (ref "U6") (pin "5") (pinfunction "SCL_5") (pintype "bidirectional"))
    )
    (net (code "15") (name "IF_NRESET") (class "Default")
      (node (ref "C1") (pin "1") (pinfunction "P$1_1") (pintype "passive"))
      (node (ref "CON2") (pin "3") (pinfunction "NRESET_3") (pintype "passive"))
      (node (ref "R1") (pin "1") (pinfunction "P$1_1") (pintype "passive"))
      (node (ref "U3") (pin "2") (pinfunction "~{RESET}/PIO0_0_2") (pintype "bidirectional"))
    )
    (net (code "16") (name "IF_SCL") (class "Default")
      (node (ref "R20") (pin "1") (pinfunction "P$1_1") (pintype "passive"))
      (node (ref "U3") (pin "10") (pinfunction "PIO0_4/SCL_10") (pintype "bidirectional"))
    )
    (net (code "17") (name "IF_SDA") (class "Default")
      (node (ref "R19") (pin "1") (pinfunction "P$1_1") (pintype "passive"))
      (node (ref "U3") (pin "11") (pinfunction "PIO0_5/SDA_11") (pintype "bidirectional"))
    )
    (net (code "18") (name "IF_SWCLK") (class "Default")
      (node (ref "CON2") (pin "4") (pinfunction "SWCLK/TCLK_4") (pintype "passive"))
      (node (ref "U3") (pin "19") (pinfunction "SWCLK/PIO0_10/SCK0/CT16B0_MAT2_19") (pintype "bidirectional"))
    )
    (net (code "19") (name "IF_SWDIO") (class "Default")
      (node (ref "CON2") (pin "2") (pinfunction "SWDIO/TMS_2") (pintype "passive"))
      (node (ref "U3") (pin "25") (pinfunction "SWDIO/PIO0_15/AD4/CT32B1_MAT2_25") (pintype "bidirectional"))
    )
    (net (code "20") (name "LED_COM_GREEN") (class "Default")
      (node (ref "LED2") (pin "C") (pinfunction "C_C") (pintype "passive"))
      (node (ref "U3") (pin "21") (pinfunction "TDI/PIO0_11/AD0/CT32B0_MAT3_21") (pintype "bidirectional"))
    )
    (net (code "21") (name "LED_DAP_BLUE") (class "Default")
      (node (ref "LED1") (pin "C") (pinfunction "C_C") (pintype "passive"))
      (node (ref "U3") (pin "12") (pinfunction "PIO0_21/CT16B1_MAT0/MOSI1_12") (pintype "bidirectional"))
    )
    (net (code "22") (name "LED_PWR_RED") (class "Default")
      (node (ref "LED3") (pin "C") (pinfunction "C_C") (pintype "passive"))
      (node (ref "U3") (pin "7") (pinfunction "PIO0_20/CT16B1_CAP0_7") (pintype "bidirectional"))
    )
    (net (code "23") (name "Net-(C6-P$1)") (class "Default")
      (node (ref "C6") (pin "1") (pinfunction "P$1_1") (pintype "passive"))
      (node (ref "Q1") (pin "P$1") (pinfunction "1_P$1") (pintype "passive"))
      (node (ref "U3") (pin "5") (pinfunction "XTALOUT_5") (pintype "output"))
    )
    (net (code "24") (name "Net-(C7-P$1)") (class "Default")
      (node (ref "C7") (pin "1") (pinfunction "P$1_1") (pintype "passive"))
      (node (ref "Q1") (pin "P$3") (pinfunction "2_P$3") (pintype "passive"))
      (node (ref "U3") (pin "4") (pinfunction "XTALIN_4") (pintype "input"))
    )
    (net (code "25") (name "Net-(C8-P$1)") (class "Default")
      (node (ref "C8") (pin "1") (pinfunction "P$1_1") (pintype "passive"))
      (node (ref "R8") (pin "2") (pinfunction "P$2_2") (pintype "passive"))
      (node (ref "U3") (pin "13") (pinfunction "USB_DM_13") (pintype "bidirectional"))
    )
    (net (code "26") (name "Net-(C9-P$1)") (class "Default")
      (node (ref "C9") (pin "1") (pinfunction "P$1_1") (pintype "passive"))
      (node (ref "R7") (pin "2") (pinfunction "P$2_2") (pintype "passive"))
      (node (ref "R9") (pin "2") (pinfunction "P$2_2") (pintype "passive"))
      (node (ref "U3") (pin "14") (pinfunction "USB_DP_14") (pintype "bidirectional"))
    )
    (net (code "27") (name "Net-(C19-P$1)") (class "Default")
      (node (ref "C19") (pin "1") (pinfunction "P$1_1") (pintype "passive"))
      (node (ref "MOD2") (pin "25") (pinfunction "SIO_00/XL1_25") (pintype "bidirectional"))
      (node (ref "Q2") (pin "X1") (pinfunction "1_X1") (pintype "passive"))
    )
    (net (code "28") (name "Net-(C20-P$1)") (class "Default")
      (node (ref "C20") (pin "1") (pinfunction "P$1_1") (pintype "passive"))
      (node (ref "MOD2") (pin "24") (pinfunction "SIO_01/XL2_24") (pintype "bidirectional"))
      (node (ref "Q2") (pin "X2") (pinfunction "2_X2") (pintype "passive"))
    )
    (net (code "29") (name "Net-(C23-P$1)") (class "Default")
      (node (ref "C23") (pin "1") (pinfunction "P$1_1") (pintype "passive"))
      (node (ref "R18") (pin "1") (pinfunction "P$1_1") (pintype "passive"))
      (node (ref "U6") (pin "1") (pinfunction "VIN+_1") (pintype "input"))
    )
    (net (code "30") (name "Net-(C23-P$2)") (class "Default")
      (node (ref "C23") (pin "2") (pinfunction "P$2_2") (pintype "passive"))
      (node (ref "R17") (pin "1") (pinfunction "P$1_1") (pintype "passive"))
      (node (ref "U6") (pin "2") (pinfunction "VIN-_2") (pintype "input"))
    )
    (net (code "31") (name "Net-(CON1-PadD+)") (class "Default")
      (node (ref "CON1") (pin "D+") (pinfunction "D+_D+") (pintype "bidirectional"))
      (node (ref "U1") (pin "6") (pinfunction "IO1_6") (pintype "bidirectional"))
    )
    (net (code "32") (name "Net-(CON1-PadD-)") (class "Default")
      (node (ref "CON1") (pin "D-") (pinfunction "D-_D-") (pintype "bidirectional"))
      (node (ref "U1") (pin "4") (pinfunction "IO2_4") (pintype "bidirectional"))
    )
    (net (code "33") (name "Net-(IC2A-O)") (class "Default")
      (node (ref "IC2") (pin "4") (pinfunction "O_4") (pintype "tri_state"))
      (node (ref "R21") (pin "1") (pinfunction "P$1_1") (pintype "passive"))
    )
    (net (code "34") (name "Net-(IC3A-O)") (class "Default")
      (node (ref "IC3") (pin "4") (pinfunction "O_4") (pintype "tri_state"))
      (node (ref "R22") (pin "1") (pinfunction "P$1_1") (pintype "passive"))
    )
    (net (code "35") (name "Net-(IC4A-O)") (class "Default")
      (node (ref "IC4") (pin "4") (pinfunction "O_4") (pintype "tri_state"))
      (node (ref "R23") (pin "1") (pinfunction "P$1_1") (pintype "passive"))
    )
    (net (code "36") (name "Net-(MOD2-SIO_09{slash}NFC1)") (class "Default")
      (node (ref "CON4") (pin "RF") (pinfunction "RF_RF") (pintype "bidirectional"))
      (node (ref "MOD2") (pin "15") (pinfunction "SIO_09/NFC1_15") (pintype "bidirectional"))
    )
    (net (code "37") (name "Net-(MOD2-SIO_10{slash}NFC2)") (class "Default")
      (node (ref "CON4") (pin "GND1") (pinfunction "GND_GND1") (pintype "bidirectional"))
      (node (ref "CON4") (pin "GND2") (pinfunction "GND_GND2") (pintype "bidirectional"))
      (node (ref "MOD2") (pin "14") (pinfunction "SIO_10/NFC2_14") (pintype "bidirectional"))
    )
    (net (code "38") (name "Net-(MOD2-SIO_25{slash}SPI_SCK)") (class "Default")
      (node (ref "LED7") (pin "C") (pinfunction "C_C") (pintype "passive"))
      (node (ref "MOD2") (pin "38") (pinfunction "SIO_25/SPI_SCK_38") (pintype "bidirectional"))
    )
    (net (code "39") (name "Net-(R2-P$2)") (class "Default")
      (node (ref "R2") (pin "2") (pinfunction "P$2_2") (pintype "passive"))
      (node (ref "U3") (pin "9") (pinfunction "PIO0_3/USB_VBUS_9") (pintype "bidirectional"))
    )
    (net (code "40") (name "Net-(R5-P$2)") (class "Default")
      (node (ref "D1") (pin "K") (pinfunction "K_K") (pintype "passive"))
      (node (ref "R5") (pin "2") (pinfunction "P$2_2") (pintype "passive"))
      (node (ref "R6") (pin "2") (pinfunction "P$2_2") (pintype "passive"))
      (node (ref "SW1") (pin "P$2") (pinfunction "S_P$2") (pintype "passive"))
    )
    (net (code "41") (name "Net-(R7-P$1)") (class "Default")
      (node (ref "R7") (pin "1") (pinfunction "P$1_1") (pintype "passive"))
      (node (ref "T1") (pin "3") (pinfunction "D_3") (pintype "passive"))
    )
    (net (code "42") (name "Net-(R10-P$1)") (class "Default")
      (node (ref "LED1") (pin "A") (pinfunction "A_A") (pintype "passive"))
      (node (ref "R10") (pin "1") (pinfunction "P$1_1") (pintype "passive"))
    )
    (net (code "43") (name "Net-(R11-P$1)") (class "Default")
      (node (ref "LED2") (pin "A") (pinfunction "A_A") (pintype "passive"))
      (node (ref "R11") (pin "1") (pinfunction "P$1_1") (pintype "passive"))
    )
    (net (code "44") (name "Net-(R12-P$1)") (class "Default")
      (node (ref "LED3") (pin "A") (pinfunction "A_A") (pintype "passive"))
      (node (ref "R12") (pin "1") (pinfunction "P$1_1") (pintype "passive"))
    )
    (net (code "45") (name "Net-(R21-P$2)") (class "Default")
      (node (ref "LED4") (pin "A") (pinfunction "A_A") (pintype "passive"))
      (node (ref "R21") (pin "2") (pinfunction "P$2_2") (pintype "passive"))
    )
    (net (code "46") (name "Net-(R22-P$2)") (class "Default")
      (node (ref "LED5") (pin "A") (pinfunction "A_A") (pintype "passive"))
      (node (ref "R22") (pin "2") (pinfunction "P$2_2") (pintype "passive"))
    )
    (net (code "47") (name "Net-(R23-P$2)") (class "Default")
      (node (ref "LED6") (pin "A") (pinfunction "A_A") (pintype "passive"))
      (node (ref "R23") (pin "2") (pinfunction "P$2_2") (pintype "passive"))
    )
    (net (code "48") (name "Net-(R24-P$2)") (class "Default")
      (node (ref "R24") (pin "2") (pinfunction "P$2_2") (pintype "passive"))
      (node (ref "SW2") (pin "P$2") (pinfunction "S_P$2") (pintype "passive"))
    )
    (net (code "49") (name "Net-(R25-P$2)") (class "Default")
      (node (ref "R25") (pin "2") (pinfunction "P$2_2") (pintype "passive"))
      (node (ref "SW3") (pin "P$2") (pinfunction "S_P$2") (pintype "passive"))
    )
    (net (code "50") (name "Net-(R26-P$1)") (class "Default")
      (node (ref "LED7") (pin "A") (pinfunction "A_A") (pintype "passive"))
      (node (ref "R26") (pin "1") (pinfunction "P$1_1") (pintype "passive"))
    )
    (net (code "51") (name "PA4") (class "Default")
      (node (ref "IC2") (pin "2") (pinfunction "I_2") (pintype "input"))
      (node (ref "MOD1") (pin "38") (pinfunction "PA4/ADC1.4_38") (pintype "bidirectional"))
    )
    (net (code "52") (name "PA5") (class "Default")
      (node (ref "IC3") (pin "2") (pinfunction "I_2") (pintype "input"))
      (node (ref "MOD1") (pin "34") (pinfunction "PA5/ADC1.5_34") (pintype "bidirectional"))
    )
    (net (code "53") (name "PB0") (class "Default")
      (node (ref "IC4") (pin "2") (pinfunction "I_2") (pintype "input"))
      (node (ref "MOD1") (pin "37") (pinfunction "PB0/ADC1.8_37") (pintype "bidirectional"))
    )
    (net (code "54") (name "PB4") (class "Default")
      (node (ref "MOD1") (pin "16") (pinfunction "PC13_16") (pintype "bidirectional"))
      (node (ref "SW3") (pin "P$1") (pinfunction "P_P$1") (pintype "passive"))
    )
    (net (code "55") (name "PB10") (class "Default")
      (node (ref "MOD1") (pin "19") (pinfunction "PB10_19") (pintype "bidirectional"))
      (node (ref "SW2") (pin "P$1") (pinfunction "P_P$1") (pintype "passive"))
    )
    (net (code "56") (name "PIO0_12") (class "Default")
      (node (ref "U3") (pin "22") (pinfunction "TMS/PIO0_12/AD1/CT32B1_CAP0_22") (pintype "bidirectional"))
    )
    (net (code "57") (name "PIO0_14") (class "Default")
      (node (ref "U3") (pin "24") (pinfunction "~{TRST}/PIO0_14/AD3/CT32B1_MAT1_24") (pintype "bidirectional"))
    )
    (net (code "58") (name "PIO0_15") (class "Default")
      (node (ref "U3") (pin "28") (pinfunction "PIO1_15/~{DCD}/CT16B0_MAT2/SCK1_28") (pintype "bidirectional"))
    )
    (net (code "59") (name "PIO0_16") (class "Default")
      (node (ref "U3") (pin "26") (pinfunction "PIO0_16/AD5/CT32B1_MAT3/WAKEUP_26") (pintype "bidirectional"))
    )
    (net (code "60") (name "PIO0_22") (class "Default")
      (node (ref "U3") (pin "20") (pinfunction "PIO0_22/AD6/CT16B1_MAT1/MISO1_20") (pintype "bidirectional"))
    )
    (net (code "61") (name "PIO0_23") (class "Default")
      (node (ref "U3") (pin "27") (pinfunction "PIO0_23/AD7_27") (pintype "bidirectional"))
    )
    (net (code "62") (name "PIO_13") (class "Default")
      (node (ref "U3") (pin "23") (pinfunction "TDO/PIO0_13/AD2/CT32B1_MAT0_23") (pintype "bidirectional"))
    )
    (net (code "63") (name "SFLASH_CS") (class "Default")
      (node (ref "MOD2") (pin "12") (pinfunction "SIO_12/SFLASH_CS_12") (pintype "bidirectional"))
      (node (ref "U5") (pin "1") (pinfunction "~{CS}_1") (pintype "bidirectional"))
    )
    (net (code "64") (name "SFLASH_MISO") (class "Default")
      (node (ref "MOD2") (pin "11") (pinfunction "SIO_14/SFLASH_MISO_11") (pintype "bidirectional"))
      (node (ref "U5") (pin "2") (pinfunction "SO_2") (pintype "bidirectional"))
    )
    (net (code "65") (name "SFLASH_MOSI") (class "Default")
      (node (ref "MOD2") (pin "8") (pinfunction "SIO_20/SFLASH_MOSI_8") (pintype "bidirectional"))
      (node (ref "U5") (pin "5") (pinfunction "SI_5") (pintype "bidirectional"))
    )
    (net (code "66") (name "SFLASH_SCK") (class "Default")
      (node (ref "MOD2") (pin "10") (pinfunction "SIO_16/SFLASH_SCK_10") (pintype "bidirectional"))
      (node (ref "U5") (pin "6") (pinfunction "SCK_6") (pintype "bidirectional"))
    )
    (net (code "67") (name "TGT_CTS") (class "Default")
      (node (ref "U3") (pin "30") (pinfunction "PIO0_17/~{RTS}/CT32B0_CAP0/SCLK_30") (pintype "bidirectional"))
    )
    (net (code "68") (name "TGT_NRESET") (class "Default")
      (node (ref "D1") (pin "A") (pinfunction "A_A") (pintype "passive"))
      (node (ref "JP4") (pin "2") (pinfunction "2_2") (pintype "passive"))
      (node (ref "U3") (pin "8") (pinfunction "PIO0_2/SSEL0/CT16B0_CAP0_8") (pintype "bidirectional"))
    )
    (net (code "69") (name "TGT_NRESET_BL652") (class "Default")
      (node (ref "C16") (pin "1") (pinfunction "P$1_1") (pintype "passive"))
      (node (ref "CON3") (pin "3") (pinfunction "NRESET_3") (pintype "passive"))
      (node (ref "JP4") (pin "3") (pinfunction "3_3") (pintype "passive"))
      (node (ref "MOD2") (pin "7") (pinfunction "~{RESET}_7") (pintype "bidirectional"))
      (node (ref "R16") (pin "1") (pinfunction "P$1_1") (pintype "passive"))
    )
    (net (code "70") (name "TGT_NRESET_EMW3166") (class "Default")
      (node (ref "C11") (pin "1") (pinfunction "P$1_1") (pintype "passive"))
      (node (ref "JP4") (pin "1") (pinfunction "1_1") (pintype "passive"))
      (node (ref "MOD1") (pin "13") (pinfunction "~{RESET}_13") (pintype "bidirectional"))
      (node (ref "R13") (pin "1") (pinfunction "P$1_1") (pintype "passive"))
    )
    (net (code "71") (name "TGT_NRESET_FB") (class "Default")
      (node (ref "R5") (pin "1") (pinfunction "P$1_1") (pintype "passive"))
      (node (ref "U3") (pin "3") (pinfunction "PIO0_1/CLKOUT/CT32B0_MAT2/USB_FTOGGLE_3") (pintype "bidirectional"))
    )
    (net (code "72") (name "TGT_NRESET_FB_ISP") (class "Default")
      (node (ref "R6") (pin "1") (pinfunction "P$1_1") (pintype "passive"))
      (node (ref "U3") (pin "1") (pinfunction "PIO1_19/~{DTR}/SSEL1_1") (pintype "bidirectional"))
    )
    (net (code "73") (name "TGT_NRST_BL652_GPIO") (class "Default")
      (node (ref "JP4") (pin "4") (pinfunction "4_4") (pintype "passive"))
      (node (ref "MOD1") (pin "33") (pinfunction "PA10_33") (pintype "bidirectional"))
    )
    (net (code "74") (name "TGT_RTS") (class "Default")
      (node (ref "R4") (pin "2") (pinfunction "P$2_2") (pintype "passive"))
      (node (ref "U3") (pin "16") (pinfunction "PIO0_7/~{CTS}_16") (pintype "bidirectional"))
    )
    (net (code "75") (name "TGT_RX") (class "Default")
      (node (ref "MOD1") (pin "12") (pinfunction "PC7/RX6_12") (pintype "bidirectional"))
      (node (ref "U3") (pin "32") (pinfunction "PIO0_19/TXD/CT32B0_MAT1_32") (pintype "bidirectional"))
    )
    (net (code "76") (name "TGT_SWCLK") (class "Default")
      (node (ref "JP6") (pin "2") (pinfunction "2_2") (pintype "passive"))
      (node (ref "R4") (pin "1") (pinfunction "P$1_1") (pintype "passive"))
      (node (ref "U3") (pin "18") (pinfunction "PIO0_9/MOSI0/CT16B0_MAT1_18") (pintype "bidirectional"))
    )
    (net (code "77") (name "TGT_SWCLK_BL652") (class "Default")
      (node (ref "CON3") (pin "4") (pinfunction "SWCLK/TCLK_4") (pintype "passive"))
      (node (ref "JP6") (pin "3") (pinfunction "3_3") (pintype "passive"))
      (node (ref "MOD2") (pin "6") (pinfunction "SWDCLK_6") (pintype "bidirectional"))
    )
    (net (code "78") (name "TGT_SWCLK_BL652_GPIO") (class "Default")
      (node (ref "JP6") (pin "4") (pinfunction "4_4") (pintype "passive"))
      (node (ref "MOD1") (pin "27") (pinfunction "PB3_27") (pintype "bidirectional"))
    )
    (net (code "79") (name "TGT_SWCLK_EMW3166") (class "Default")
      (node (ref "JP6") (pin "1") (pinfunction "1_1") (pintype "passive"))
      (node (ref "MOD1") (pin "25") (pinfunction "PA14/SWCLK_25") (pintype "bidirectional"))
    )
    (net (code "80") (name "TGT_SWDIO") (class "Default")
      (node (ref "JP5") (pin "2") (pinfunction "2_2") (pintype "passive"))
      (node (ref "U3") (pin "17") (pinfunction "PIO0_8/MISO0/CT16B0_MAT0_17") (pintype "bidirectional"))
    )
    (net (code "81") (name "TGT_SWDIO_BL652") (class "Default")
      (node (ref "CON3") (pin "2") (pinfunction "SWDIO/TMS_2") (pintype "passive"))
      (node (ref "JP5") (pin "3") (pinfunction "3_3") (pintype "passive"))
      (node (ref "MOD2") (pin "5") (pinfunction "SWDIO_5") (pintype "bidirectional"))
    )
    (net (code "82") (name "TGT_SWDIO_BL652_GPIO") (class "Default")
      (node (ref "JP5") (pin "4") (pinfunction "4_4") (pintype "passive"))
      (node (ref "MOD1") (pin "31") (pinfunction "PB4_31") (pintype "bidirectional"))
    )
    (net (code "83") (name "TGT_SWDIO_EMW3166") (class "Default")
      (node (ref "JP5") (pin "1") (pinfunction "1_1") (pintype "passive"))
      (node (ref "MOD1") (pin "26") (pinfunction "PA13/SWDIO_26") (pintype "bidirectional"))
    )
    (net (code "84") (name "TGT_TX") (class "Default")
      (node (ref "MOD1") (pin "8") (pinfunction "PC6/TX6_8") (pintype "bidirectional"))
      (node (ref "U3") (pin "31") (pinfunction "PIO0_18/RXD/CT32B0_MAT0_31") (pintype "bidirectional"))
    )
    (net (code "85") (name "USB-D+") (class "Default")
      (node (ref "R9") (pin "1") (pinfunction "P$1_1") (pintype "passive"))
      (node (ref "U1") (pin "1") (pinfunction "IO1_1") (pintype "bidirectional"))
    )
    (net (code "86") (name "USB-D-") (class "Default")
      (node (ref "R8") (pin "1") (pinfunction "P$1_1") (pintype "passive"))
      (node (ref "U1") (pin "3") (pinfunction "IO2_3") (pintype "bidirectional"))
    )
    (net (code "87") (name "USB-SCON") (class "Default")
      (node (ref "T1") (pin "1") (pinfunction "G_1") (pintype "passive"))
      (node (ref "U3") (pin "15") (pinfunction "PIO0_6/~{USB_CONNECT}/SCK0_15") (pintype "bidirectional"))
    )
    (net (code "88") (name "unconnected-(CON2-SWO{slash}TDO-Pad6)") (class "Default")
      (node (ref "CON2") (pin "6") (pinfunction "SWO/TDO_6") (pintype "passive"))
    )
    (net (code "89") (name "unconnected-(CON3-SWO{slash}TDO-Pad6)") (class "Default")
      (node (ref "CON3") (pin "6") (pinfunction "SWO/TDO_6") (pintype "passive"))
    )
    (net (code "90") (name "unconnected-(IC1-NC1-Pad1)") (class "Default")
      (node (ref "IC1") (pin "1") (pinfunction "NC1_1") (pintype "bidirectional"))
    )
    (net (code "91") (name "unconnected-(IC1-NC2-Pad2)") (class "Default")
      (node (ref "IC1") (pin "2") (pinfunction "NC2_2") (pintype "bidirectional"))
    )
    (net (code "92") (name "unconnected-(IC1-NC3-Pad3)") (class "Default")
      (node (ref "IC1") (pin "3") (pinfunction "NC3_3") (pintype "bidirectional"))
    )
    (net (code "93") (name "unconnected-(IC1-NC7-Pad7)") (class "Default")
      (node (ref "IC1") (pin "7") (pinfunction "NC7_7") (pintype "bidirectional"))
    )
    (net (code "94") (name "unconnected-(MOD1-ANT-Pad41)") (class "Default")
      (node (ref "MOD1") (pin "41") (pinfunction "ANT_41") (pintype "bidirectional"))
    )
    (net (code "95") (name "unconnected-(MOD1-PB2-Pad2)") (class "Default")
      (node (ref "MOD1") (pin "2") (pinfunction "PB2_2") (pintype "bidirectional"))
    )
    (net (code "96") (name "unconnected-(MOD1-PB12{slash}NSS2-Pad5)") (class "Default")
      (node (ref "MOD1") (pin "5") (pinfunction "PB12/NSS2_5") (pintype "bidirectional"))
    )
    (net (code "97") (name "unconnected-(MOD1-PC0-Pad14)") (class "Default")
      (node (ref "MOD1") (pin "14") (pinfunction "PC0_14") (pintype "bidirectional"))
    )
    (net (code "98") (name "unconnected-(MOD2-SIO_02{slash}AIN0-Pad23)") (class "Default")
      (node (ref "MOD2") (pin "23") (pinfunction "SIO_02/AIN0_23") (pintype "bidirectional"))
    )
    (net (code "99") (name "unconnected-(MOD2-SIO_03{slash}AIN1-Pad22)") (class "Default")
      (node (ref "MOD2") (pin "22") (pinfunction "SIO_03/AIN1_22") (pintype "bidirectional"))
    )
    (net (code "100") (name "unconnected-(MOD2-SIO_04{slash}AIN2-Pad21)") (class "Default")
      (node (ref "MOD2") (pin "21") (pinfunction "SIO_04/AIN2_21") (pintype "bidirectional"))
    )
    (net (code "101") (name "unconnected-(MOD2-SIO_11-Pad13)") (class "Default")
      (node (ref "MOD2") (pin "13") (pinfunction "SIO_11_13") (pintype "bidirectional"))
    )
    (net (code "102") (name "unconnected-(MOD2-SIO_13{slash}~{AUTORUN}-Pad28)") (class "Default")
      (node (ref "MOD2") (pin "28") (pinfunction "SIO_13/~{AUTORUN}_28") (pintype "bidirectional"))
    )
    (net (code "103") (name "unconnected-(MOD2-SIO_15-Pad29)") (class "Default")
      (node (ref "MOD2") (pin "29") (pinfunction "SIO_15_29") (pintype "bidirectional"))
    )
    (net (code "104") (name "unconnected-(MOD2-SIO_17-Pad30)") (class "Default")
      (node (ref "MOD2") (pin "30") (pinfunction "SIO_17_30") (pintype "bidirectional"))
    )
    (net (code "105") (name "unconnected-(MOD2-SIO_18-Pad9)") (class "Default")
      (node (ref "MOD2") (pin "9") (pinfunction "SIO_18_9") (pintype "bidirectional"))
    )
    (net (code "106") (name "unconnected-(MOD2-SIO_19-Pad31)") (class "Default")
      (node (ref "MOD2") (pin "31") (pinfunction "SIO_19_31") (pintype "bidirectional"))
    )
    (net (code "107") (name "unconnected-(MOD2-SIO_22-Pad4)") (class "Default")
      (node (ref "MOD2") (pin "4") (pinfunction "SIO_22_4") (pintype "bidirectional"))
    )
    (net (code "108") (name "unconnected-(MOD2-SIO_23{slash}SPI_MOSI-Pad3)") (class "Default")
      (node (ref "MOD2") (pin "3") (pinfunction "SIO_23/SPI_MOSI_3") (pintype "bidirectional"))
    )
    (net (code "109") (name "unconnected-(MOD2-SIO_24{slash}SPI_MISO-Pad2)") (class "Default")
      (node (ref "MOD2") (pin "2") (pinfunction "SIO_24/SPI_MISO_2") (pintype "bidirectional"))
    )
    (net (code "110") (name "unconnected-(MOD2-SIO_28{slash}AIN4-Pad35)") (class "Default")
      (node (ref "MOD2") (pin "35") (pinfunction "SIO_28/AIN4_35") (pintype "bidirectional"))
    )
    (net (code "111") (name "unconnected-(MOD2-SIO_29{slash}AIN5-Pad34)") (class "Default")
      (node (ref "MOD2") (pin "34") (pinfunction "SIO_29/AIN5_34") (pintype "bidirectional"))
    )
    (net (code "112") (name "unconnected-(MOD2-SIO_30{slash}AIN6-Pad33)") (class "Default")
      (node (ref "MOD2") (pin "33") (pinfunction "SIO_30/AIN6_33") (pintype "bidirectional"))
    )
    (net (code "113") (name "unconnected-(MOD2-SIO_31{slash}AIN7-Pad32)") (class "Default")
      (node (ref "MOD2") (pin "32") (pinfunction "SIO_31/AIN7_32") (pintype "bidirectional"))
    )
  )
)
